# Mango.net
KiCad netlist of a schematic drawn in EAGLE
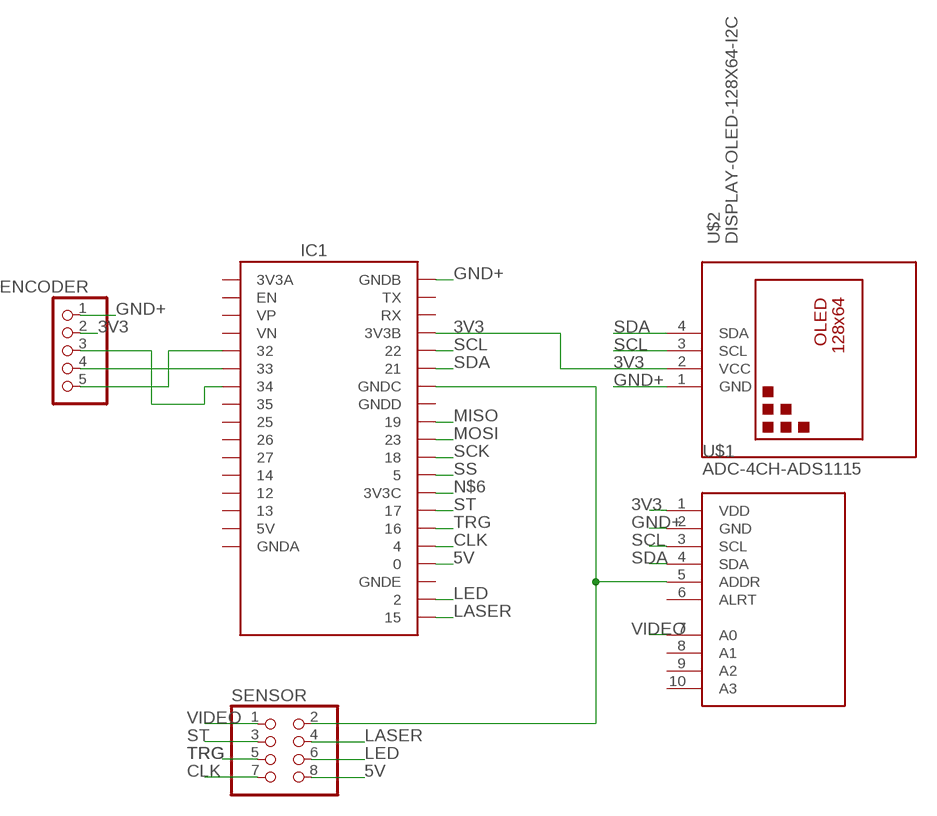
[diagram p0: schematic, sheet 1]

(export (version "E")
  (design (tool "Eeschema 10.0.6"))
  (components
    (comp (ref "ENCODER")
      (value "PINHD-1X5")
      (footprint "eagle-import:1X05")
      (libsource (lib "eagle-import") (part "PINHD-1X5"))
    )
    (comp (ref "IC1")
      (value "SSFD_LOLIN32_WEMOS_CHINA_W_BATT")
      (footprint "eagle-import:SSFD_LOLIN32_WEMOS_CHINA_W_BATT")
      (libsource (lib "eagle-import") (part "SSFD_LOLIN32_WEMOS_CHINA_W_BATT"))
    )
    (comp (ref "SENSOR")
      (value "PINHD-2X4")
      (footprint "eagle-import:2X04")
      (libsource (lib "eagle-import") (part "PINHD-2X4"))
    )
    (comp (ref "U$1")
      (value "ADC-4CH-ADS1115")
      (footprint "eagle-import:ADC-4CH-ADS1115")
      (libsource (lib "eagle-import") (part "ADC-4CH-ADS1115"))
    )
    (comp (ref "U$2")
      (value "DISPLAY-OLED-128X64-I2C")
      (footprint "eagle-import:DISPLAY-OLED-128X64-I2C")
      (libsource (lib "eagle-import") (part "DISPLAY-OLED-128X64-I2C"))
    )
  )
  (nets
    (net (code "1") (name "/3V3") (class "Default")
      (node (ref "ENCODER") (pin "2") (pinfunction "2_2") (pintype "passive"))
      (node (ref "IC1") (pin "3V3B") (pinfunction "3V3B_3V3B") (pintype "bidirectional"))
      (node (ref "U$1") (pin "1") (pinfunction "VDD_1") (pintype "power_in"))
      (node (ref "U$2") (pin "2") (pinfunction "VCC_2") (pintype "power_in"))
    )
    (net (code "2") (name "/5V") (class "Default")
      (node (ref "IC1") (pin "0") (pinfunction "0_0") (pintype "bidirectional"))
      (node (ref "SENSOR") (pin "8") (pinfunction "8_8") (pintype "passive"))
    )
    (net (code "3") (name "/CLK") (class "Default")
      (node (ref "IC1") (pin "4") (pinfunction "4_4") (pintype "bidirectional"))
      (node (ref "SENSOR") (pin "7") (pinfunction "7_7") (pintype "passive"))
    )
    (net (code "4") (name "/GND+") (class "Default")
      (node (ref "ENCODER") (pin "1") (pinfunction "1_1") (pintype "passive"))
      (node (ref "IC1") (pin "GNDB") (pinfunction "GNDB_GNDB") (pintype "bidirectional"))
      (node (ref "U$1") (pin "2") (pinfunction "GND_2") (pintype "power_in"))
      (node (ref "U$2") (pin "1") (pinfunction "GND_1") (pintype "power_in"))
    )
    (net (code "5") (name "/LASER") (class "Default")
      (node (ref "IC1") (pin "15") (pinfunction "15_15") (pintype "bidirectional"))
      (node (ref "SENSOR") (pin "4") (pinfunction "4_4") (pintype "passive"))
    )
    (net (code "6") (name "/LED") (class "Default")
      (node (ref "IC1") (pin "2") (pinfunction "2_2") (pintype "bidirectional"))
      (node (ref "SENSOR") (pin "6") (pinfunction "6_6") (pintype "passive"))
    )
    (net (code "7") (name "/MISO") (class "Default")
      (node (ref "IC1") (pin "19") (pinfunction "19_19") (pintype "bidirectional"))
    )
    (net (code "8") (name "/MOSI") (class "Default")
      (node (ref "IC1") (pin "23") (pinfunction "23_23") (pintype "bidirectional"))
    )
    (net (code "9") (name "/N$6") (class "Default")
      (node (ref "IC1") (pin "3V3C") (pinfunction "3V3C_3V3C") (pintype "bidirectional"))
    )
    (net (code "10") (name "/SCK") (class "Default")
      (node (ref "IC1") (pin "18") (pinfunction "18_18") (pintype "bidirectional"))
    )
    (net (code "11") (name "/SCL") (class "Default")
      (node (ref "IC1") (pin "22") (pinfunction "22_22") (pintype "bidirectional"))
      (node (ref "U$1") (pin "3") (pinfunction "SCL_3") (pintype "bidirectional"))
      (node (ref "U$2") (pin "3") (pinfunction "SCL_3") (pintype "bidirectional"))
    )
    (net (code "12") (name "/SDA") (class "Default")
      (node (ref "IC1") (pin "21") (pinfunction "21_21") (pintype "bidirectional"))
      (node (ref "U$1") (pin "4") (pinfunction "SDA_4") (pintype "bidirectional"))
      (node (ref "U$2") (pin "4") (pinfunction "SDA_4") (pintype "bidirectional"))
    )
    (net (code "13") (name "/SS") (class "Default")
      (node (ref "IC1") (pin "5") (pinfunction "5_5") (pintype "bidirectional"))
    )
    (net (code "14") (name "/ST") (class "Default")
      (node (ref "IC1") (pin "17") (pinfunction "17_17") (pintype "bidirectional"))
      (node (ref "SENSOR") (pin "3") (pinfunction "3_3") (pintype "passive"))
    )
    (net (code "15") (name "/TRG") (class "Default")
      (node (ref "IC1") (pin "16") (pinfunction "16_16") (pintype "bidirectional"))
      (node (ref "SENSOR") (pin "5") (pinfunction "5_5") (pintype "passive"))
    )
    (net (code "16") (name "/VIDEO") (class "Default")
      (node (ref "SENSOR") (pin "1") (pinfunction "1_1") (pintype "passive"))
      (node (ref "U$1") (pin "7") (pinfunction "A0_7") (pintype "input"))
    )
    (net (code "17") (name "Net-(ENCODER-Pad3)") (class "Default")
      (node (ref "ENCODER") (pin "3") (pinfunction "3_3") (pintype "passive"))
      (node (ref "IC1") (pin "34") (pinfunction "34_34") (pintype "bidirectional"))
    )
    (net (code "18") (name "Net-(ENCODER-Pad4)") (class "Default")
      (node (ref "ENCODER") (pin "4") (pinfunction "4_4") (pintype "passive"))
      (node (ref "IC1") (pin "33") (pinfunction "33_33") (pintype "bidirectional"))
    )
    (net (code "19") (name "Net-(ENCODER-Pad5)") (class "Default")
      (node (ref "ENCODER") (pin "5") (pinfunction "5_5") (pintype "passive"))
      (node (ref "IC1") (pin "32") (pinfunction "32_32") (pintype "bidirectional"))
    )
    (net (code "20") (name "Net-(U$1-ADDR)") (class "Default")
      (node (ref "IC1") (pin "GNDC") (pinfunction "GNDC_GNDC") (pintype "bidirectional"))
      (node (ref "SENSOR") (pin "2") (pinfunction "2_2") (pintype "passive"))
      (node (ref "U$1") (pin "5") (pinfunction "ADDR_5") (pintype "bidirectional"))
    )
    (net (code "21") (name "unconnected-(IC1-Pad3V3A)") (class "Default")
      (node (ref "IC1") (pin "3V3A") (pinfunction "3V3A_3V3A") (pintype "bidirectional"))
    )
    (net (code "22") (name "unconnected-(IC1-Pad5V)") (class "Default")
      (node (ref "IC1") (pin "5V") (pinfunction "5V_5V") (pintype "bidirectional"))
    )
    (net (code "23") (name "unconnected-(IC1-Pad12)") (class "Default")
      (node (ref "IC1") (pin "12") (pinfunction "12_12") (pintype "bidirectional"))
    )
    (net (code "24") (name "unconnected-(IC1-Pad13)") (class "Default")
      (node (ref "IC1") (pin "13") (pinfunction "13_13") (pintype "bidirectional"))
    )
    (net (code "25") (name "unconnected-(IC1-Pad14)") (class "Default")
      (node (ref "IC1") (pin "14") (pinfunction "14_14") (pintype "bidirectional"))
    )
    (net (code "26") (name "unconnected-(IC1-Pad25)") (class "Default")
      (node (ref "IC1") (pin "25") (pinfunction "25_25") (pintype "bidirectional"))
    )
    (net (code "27") (name "unconnected-(IC1-Pad26)") (class "Default")
      (node (ref "IC1") (pin "26") (pinfunction "26_26") (pintype "bidirectional"))
    )
    (net (code "28") (name "unconnected-(IC1-Pad27)") (class "Default")
      (node (ref "IC1") (pin "27") (pinfunction "27_27") (pintype "bidirectional"))
    )
    (net (code "29") (name "unconnected-(IC1-Pad35)") (class "Default")
      (node (ref "IC1") (pin "35") (pinfunction "35_35") (pintype "bidirectional"))
    )
    (net (code "30") (name "unconnected-(IC1-PadEN)") (class "Default")
      (node (ref "IC1") (pin "EN") (pinfunction "EN_EN") (pintype "bidirectional"))
    )
    (net (code "31") (name "unconnected-(IC1-PadGNDA)") (class "Default")
      (node (ref "IC1") (pin "GNDA") (pinfunction "GNDA_GNDA") (pintype "bidirectional"))
    )
    (net (code "32") (name "unconnected-(IC1-PadGNDD)") (class "Default")
      (node (ref "IC1") (pin "GNDD") (pinfunction "GNDD_GNDD") (pintype "bidirectional"))
    )
    (net (code "33") (name "unconnected-(IC1-PadGNDE)") (class "Default")
      (node (ref "IC1") (pin "GNDE") (pinfunction "GNDE_GNDE") (pintype "bidirectional"))
    )
    (net (code "34") (name "unconnected-(IC1-PadRX)") (class "Default")
      (node (ref "IC1") (pin "RX") (pinfunction "RX_RX") (pintype "bidirectional"))
    )
    (net (code "35") (name "unconnected-(IC1-PadTX)") (class "Default")
      (node (ref "IC1") (pin "TX") (pinfunction "TX_TX") (pintype "bidirectional"))
    )
    (net (code "36") (name "unconnected-(IC1-PadVN)") (class "Default")
      (node (ref "IC1") (pin "VN") (pinfunction "VN_VN") (pintype "bidirectional"))
    )
    (net (code "37") (name "unconnected-(IC1-PadVP)") (class "Default")
      (node (ref "IC1") (pin "VP") (pinfunction "VP_VP") (pintype "bidirectional"))
    )
    (net (code "38") (name "unconnected-(U$1-A1-Pad8)") (class "Default")
      (node (ref "U$1") (pin "8") (pinfunction "A1_8") (pintype "input"))
    )
    (net (code "39") (name "unconnected-(U$1-A2-Pad9)") (class "Default")
      (node (ref "U$1") (pin "9") (pinfunction "A2_9") (pintype "input"))
    )
    (net (code "40") (name "unconnected-(U$1-A3-Pad10)") (class "Default")
      (node (ref "U$1") (pin "10") (pinfunction "A3_10") (pintype "input"))
    )
    (net (code "41") (name "unconnected-(U$1-ALRT-Pad6)") (class "Default")
      (node (ref "U$1") (pin "6") (pinfunction "ALRT_6") (pintype "bidirectional"))
    )
  )
)
